# G1000_Buttons_Bottom.net
KiCad netlist of a schematic drawn in EasyEDA
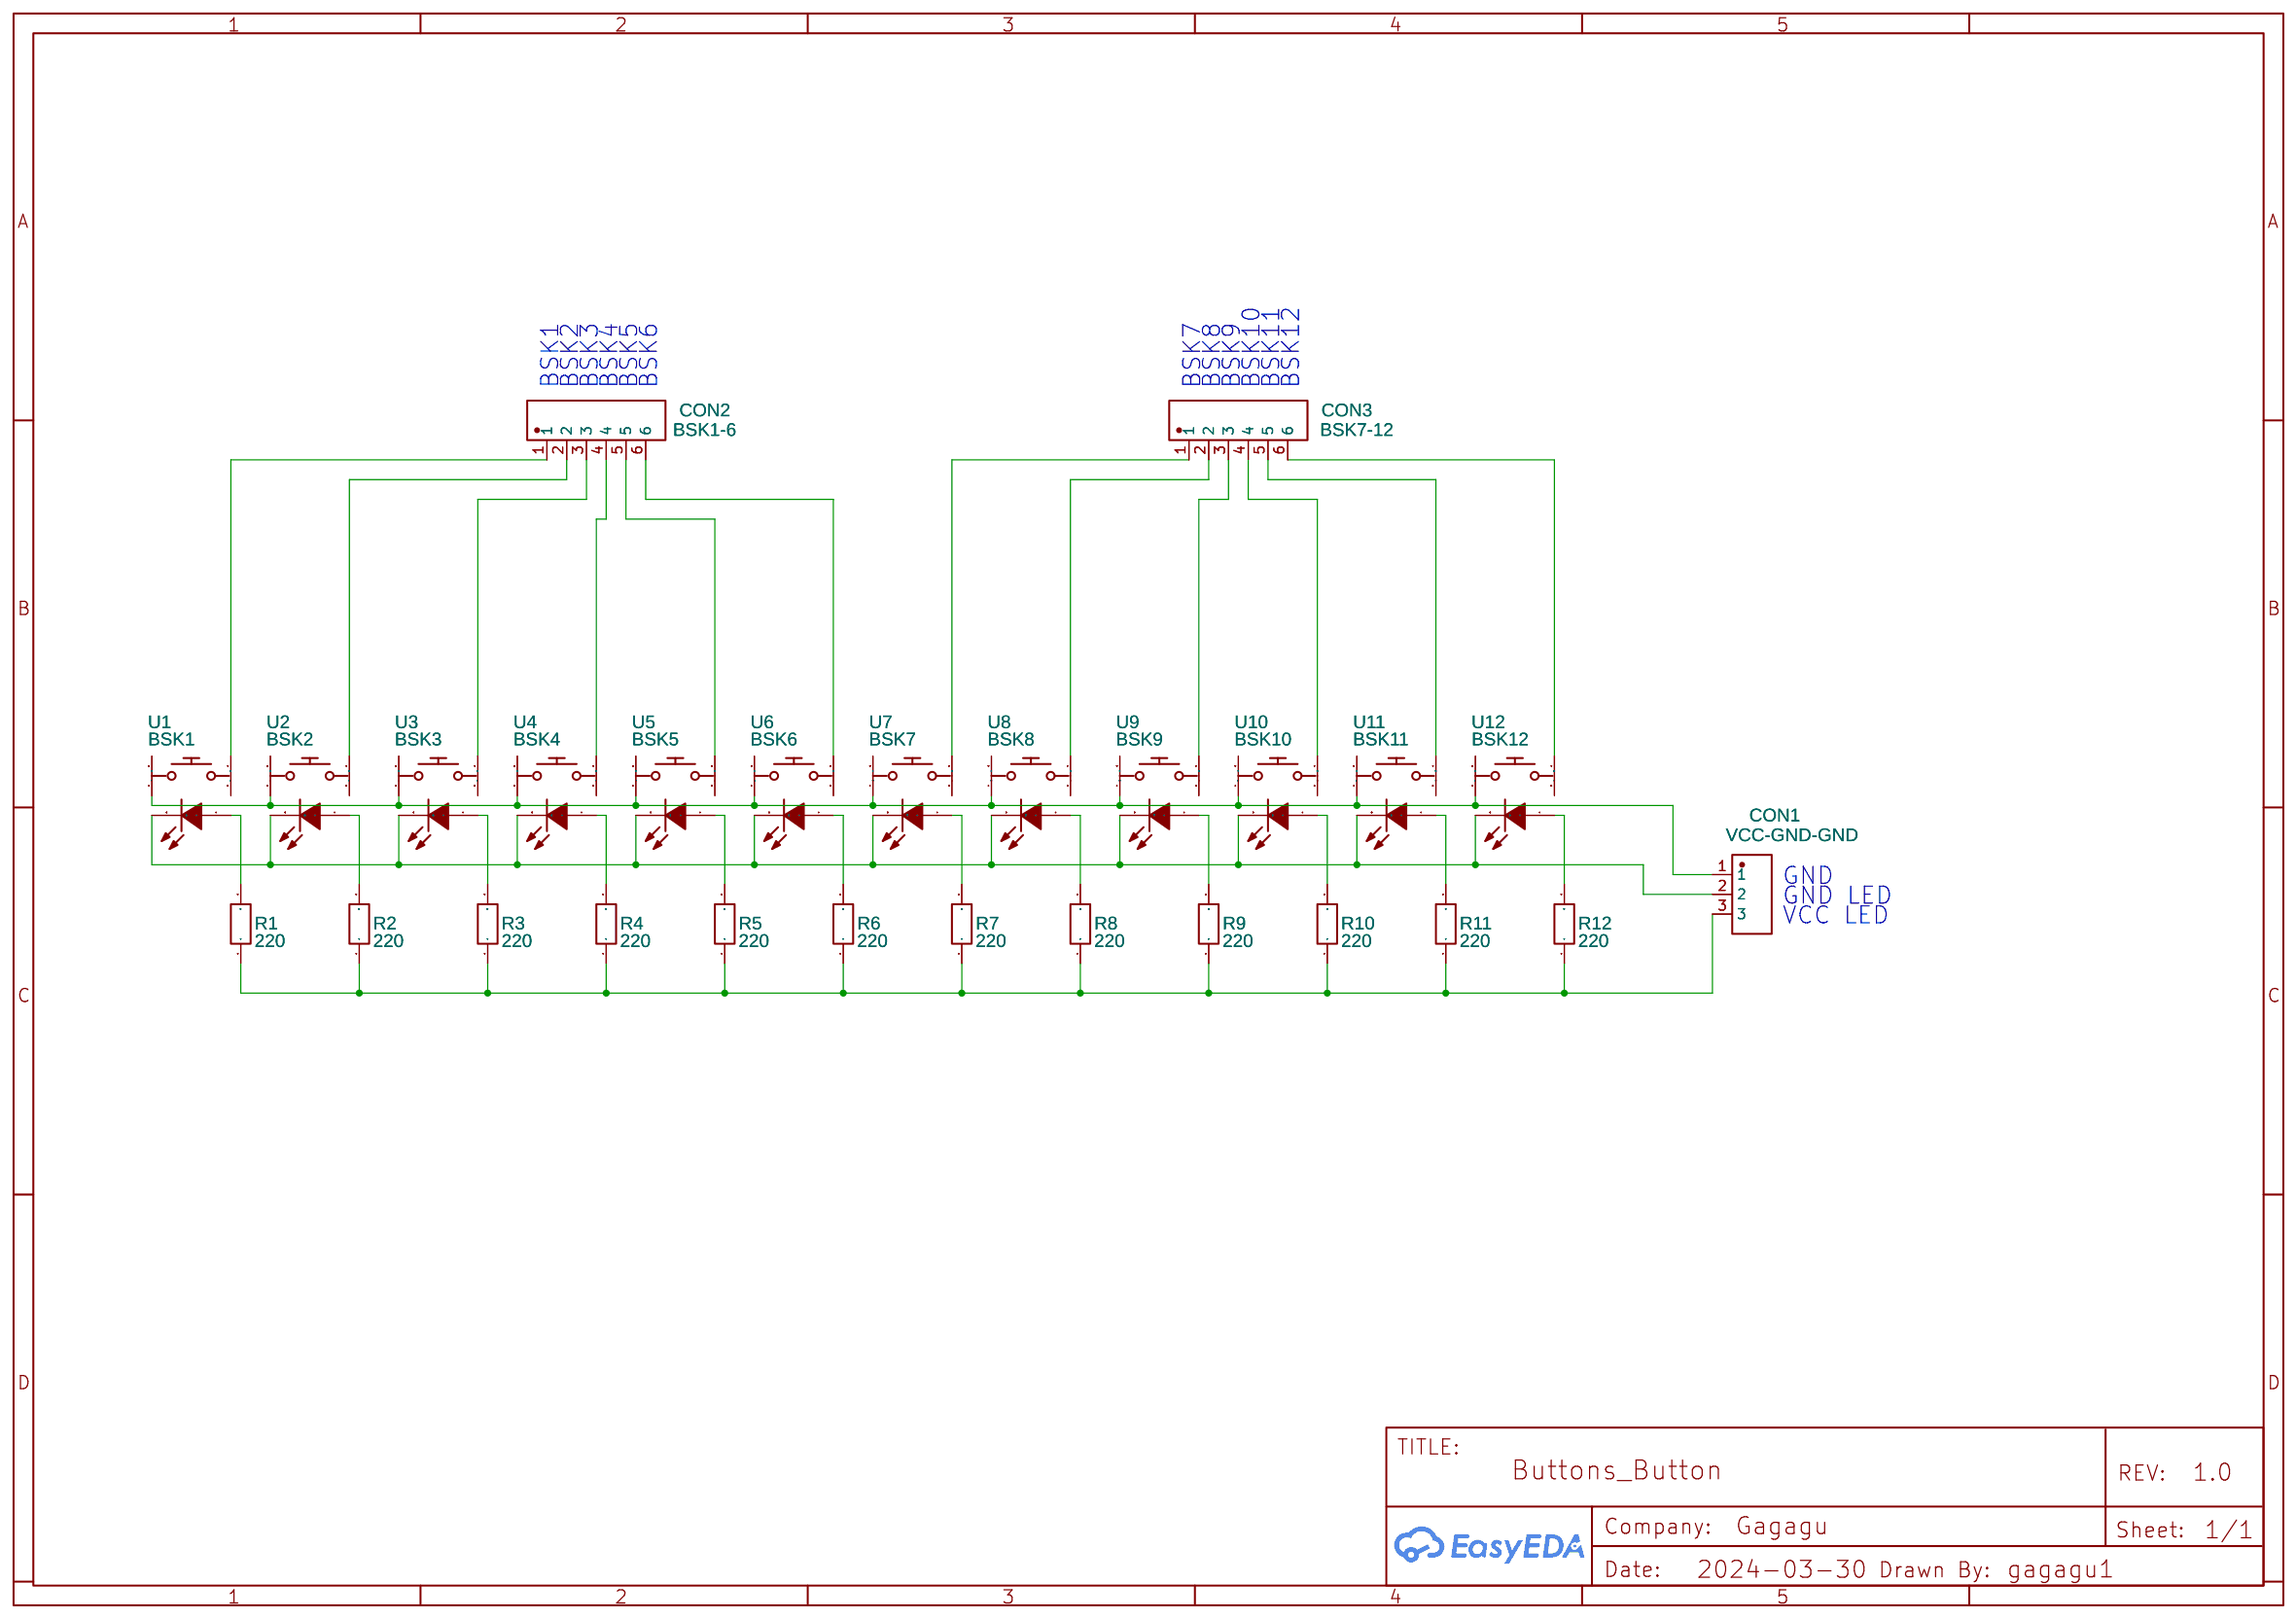
[diagram p0: schematic sheet]

(export (version "E")
  (design (tool "Eeschema 10.0.6"))
  (components
    (comp (ref "CON1")
      (value "VCC-GND-GND")
      (fields (field (name "Manufacturer Part") "HC-XH-3A-G") (field (name "Manufacturer") "HCTL(华灿天禄)"))
      (libsource (lib "") (part "HC-XH-3A-G"))
    )
    (comp (ref "CON2")
      (value "BSK1-6")
      (fields (field (name "Manufacturer Part") "XH-6A") (field (name "Manufacturer") "CAX"))
      (libsource (lib "") (part "ARUN-CONN-TH_XH-6A"))
    )
    (comp (ref "CON3")
      (value "BSK7-12")
      (fields (field (name "Manufacturer Part") "XH-6A") (field (name "Manufacturer") "CAX"))
      (libsource (lib "") (part "ARUN-CONN-TH_XH-6A"))
    )
    (comp (ref "R1") (value "220") (libsource (lib "") (part "R_AXIAL-0.4_EU")))
    (comp (ref "R2") (value "220") (libsource (lib "") (part "R_AXIAL-0.4_EU")))
    (comp (ref "R3") (value "220") (libsource (lib "") (part "R_AXIAL-0.4_EU")))
    (comp (ref "R4") (value "220") (libsource (lib "") (part "R_AXIAL-0.4_EU")))
    (comp (ref "R5") (value "220") (libsource (lib "") (part "R_AXIAL-0.4_EU")))
    (comp (ref "R6") (value "220") (libsource (lib "") (part "R_AXIAL-0.4_EU")))
    (comp (ref "R7") (value "220") (libsource (lib "") (part "R_AXIAL-0.4_EU")))
    (comp (ref "R8") (value "220") (libsource (lib "") (part "R_AXIAL-0.4_EU")))
    (comp (ref "R9") (value "220") (libsource (lib "") (part "R_AXIAL-0.4_EU")))
    (comp (ref "R10") (value "220") (libsource (lib "") (part "R_AXIAL-0.4_EU")))
    (comp (ref "R11") (value "220") (libsource (lib "") (part "R_AXIAL-0.4_EU")))
    (comp (ref "R12") (value "220") (libsource (lib "") (part "R_AXIAL-0.4_EU")))
    (comp (ref "U1") (value "BSK1") (libsource (lib "") (part "6X6_LED+PUSHBUTTON V2")))
    (comp (ref "U2") (value "BSK2") (libsource (lib "") (part "6X6_LED+PUSHBUTTON V2")))
    (comp (ref "U3") (value "BSK3") (libsource (lib "") (part "6X6_LED+PUSHBUTTON V2")))
    (comp (ref "U4") (value "BSK4") (libsource (lib "") (part "6X6_LED+PUSHBUTTON V2")))
    (comp (ref "U5") (value "BSK5") (libsource (lib "") (part "6X6_LED+PUSHBUTTON V2")))
    (comp (ref "U6") (value "BSK6") (libsource (lib "") (part "6X6_LED+PUSHBUTTON V2")))
    (comp (ref "U7") (value "BSK7") (libsource (lib "") (part "6X6_LED+PUSHBUTTON V2")))
    (comp (ref "U8") (value "BSK8") (libsource (lib "") (part "6X6_LED+PUSHBUTTON V2")))
    (comp (ref "U9") (value "BSK9") (libsource (lib "") (part "6X6_LED+PUSHBUTTON V2")))
    (comp (ref "U10") (value "BSK10") (libsource (lib "") (part "6X6_LED+PUSHBUTTON V2")))
    (comp (ref "U11") (value "BSK11") (libsource (lib "") (part "6X6_LED+PUSHBUTTON V2")))
    (comp (ref "U12") (value "BSK12") (libsource (lib "") (part "6X6_LED+PUSHBUTTON V2")))
  )
  (nets
    (net (code "1") (name "Net-(CON1-Pad1)") (class "Default")
      (node (ref "CON1") (pin "1") (pinfunction "1_1") (pintype "unspecified"))
      (node (ref "U1") (pin "4") (pinfunction "4_4") (pintype "unspecified"))
      (node (ref "U10") (pin "4") (pinfunction "4_4") (pintype "unspecified"))
      (node (ref "U11") (pin "4") (pinfunction "4_4") (pintype "unspecified"))
      (node (ref "U12") (pin "4") (pinfunction "4_4") (pintype "unspecified"))
      (node (ref "U2") (pin "4") (pinfunction "4_4") (pintype "unspecified"))
      (node (ref "U3") (pin "4") (pinfunction "4_4") (pintype "unspecified"))
      (node (ref "U4") (pin "4") (pinfunction "4_4") (pintype "unspecified"))
      (node (ref "U5") (pin "4") (pinfunction "4_4") (pintype "unspecified"))
      (node (ref "U6") (pin "4") (pinfunction "4_4") (pintype "unspecified"))
      (node (ref "U7") (pin "4") (pinfunction "4_4") (pintype "unspecified"))
      (node (ref "U8") (pin "4") (pinfunction "4_4") (pintype "unspecified"))
      (node (ref "U9") (pin "4") (pinfunction "4_4") (pintype "unspecified"))
    )
    (net (code "2") (name "Net-(CON1-Pad2)") (class "Default")
      (node (ref "CON1") (pin "2") (pinfunction "2_2") (pintype "unspecified"))
      (node (ref "U1") (pin "C") (pinfunction "C_C") (pintype "unspecified"))
      (node (ref "U10") (pin "C") (pinfunction "C_C") (pintype "unspecified"))
      (node (ref "U11") (pin "C") (pinfunction "C_C") (pintype "unspecified"))
      (node (ref "U12") (pin "C") (pinfunction "C_C") (pintype "unspecified"))
      (node (ref "U2") (pin "C") (pinfunction "C_C") (pintype "unspecified"))
      (node (ref "U3") (pin "C") (pinfunction "C_C") (pintype "unspecified"))
      (node (ref "U4") (pin "C") (pinfunction "C_C") (pintype "unspecified"))
      (node (ref "U5") (pin "C") (pinfunction "C_C") (pintype "unspecified"))
      (node (ref "U6") (pin "C") (pinfunction "C_C") (pintype "unspecified"))
      (node (ref "U7") (pin "C") (pinfunction "C_C") (pintype "unspecified"))
      (node (ref "U8") (pin "C") (pinfunction "C_C") (pintype "unspecified"))
      (node (ref "U9") (pin "C") (pinfunction "C_C") (pintype "unspecified"))
    )
    (net (code "3") (name "Net-(CON1-Pad3)") (class "Default")
      (node (ref "CON1") (pin "3") (pinfunction "3_3") (pintype "unspecified"))
      (node (ref "R1") (pin "1") (pinfunction "1_1") (pintype "unspecified"))
      (node (ref "R10") (pin "1") (pinfunction "1_1") (pintype "unspecified"))
      (node (ref "R11") (pin "1") (pinfunction "1_1") (pintype "unspecified"))
      (node (ref "R12") (pin "1") (pinfunction "1_1") (pintype "unspecified"))
      (node (ref "R2") (pin "1") (pinfunction "1_1") (pintype "unspecified"))
      (node (ref "R3") (pin "1") (pinfunction "1_1") (pintype "unspecified"))
      (node (ref "R4") (pin "1") (pinfunction "1_1") (pintype "unspecified"))
      (node (ref "R5") (pin "1") (pinfunction "1_1") (pintype "unspecified"))
      (node (ref "R6") (pin "1") (pinfunction "1_1") (pintype "unspecified"))
      (node (ref "R7") (pin "1") (pinfunction "1_1") (pintype "unspecified"))
      (node (ref "R8") (pin "1") (pinfunction "1_1") (pintype "unspecified"))
      (node (ref "R9") (pin "1") (pinfunction "1_1") (pintype "unspecified"))
    )
    (net (code "4") (name "Net-(CON2-Pad1)") (class "Default")
      (node (ref "CON2") (pin "1") (pinfunction "1_1") (pintype "unspecified"))
      (node (ref "U1") (pin "1") (pinfunction "1_1") (pintype "unspecified"))
    )
    (net (code "5") (name "Net-(CON2-Pad2)") (class "Default")
      (node (ref "CON2") (pin "2") (pinfunction "2_2") (pintype "unspecified"))
      (node (ref "U2") (pin "1") (pinfunction "1_1") (pintype "unspecified"))
    )
    (net (code "6") (name "Net-(CON2-Pad3)") (class "Default")
      (node (ref "CON2") (pin "3") (pinfunction "3_3") (pintype "unspecified"))
      (node (ref "U3") (pin "1") (pinfunction "1_1") (pintype "unspecified"))
    )
    (net (code "7") (name "Net-(CON2-Pad4)") (class "Default")
      (node (ref "CON2") (pin "4") (pinfunction "4_4") (pintype "unspecified"))
      (node (ref "U4") (pin "1") (pinfunction "1_1") (pintype "unspecified"))
    )
    (net (code "8") (name "Net-(CON2-Pad5)") (class "Default")
      (node (ref "CON2") (pin "5") (pinfunction "5_5") (pintype "unspecified"))
      (node (ref "U5") (pin "1") (pinfunction "1_1") (pintype "unspecified"))
    )
    (net (code "9") (name "Net-(CON2-Pad6)") (class "Default")
      (node (ref "CON2") (pin "6") (pinfunction "6_6") (pintype "unspecified"))
      (node (ref "U6") (pin "1") (pinfunction "1_1") (pintype "unspecified"))
    )
    (net (code "10") (name "Net-(CON3-Pad1)") (class "Default")
      (node (ref "CON3") (pin "1") (pinfunction "1_1") (pintype "unspecified"))
      (node (ref "U7") (pin "1") (pinfunction "1_1") (pintype "unspecified"))
    )
    (net (code "11") (name "Net-(CON3-Pad2)") (class "Default")
      (node (ref "CON3") (pin "2") (pinfunction "2_2") (pintype "unspecified"))
      (node (ref "U8") (pin "1") (pinfunction "1_1") (pintype "unspecified"))
    )
    (net (code "12") (name "Net-(CON3-Pad3)") (class "Default")
      (node (ref "CON3") (pin "3") (pinfunction "3_3") (pintype "unspecified"))
      (node (ref "U9") (pin "1") (pinfunction "1_1") (pintype "unspecified"))
    )
    (net (code "13") (name "Net-(CON3-Pad4)") (class "Default")
      (node (ref "CON3") (pin "4") (pinfunction "4_4") (pintype "unspecified"))
      (node (ref "U10") (pin "1") (pinfunction "1_1") (pintype "unspecified"))
    )
    (net (code "14") (name "Net-(CON3-Pad5)") (class "Default")
      (node (ref "CON3") (pin "5") (pinfunction "5_5") (pintype "unspecified"))
      (node (ref "U11") (pin "1") (pinfunction "1_1") (pintype "unspecified"))
    )
    (net (code "15") (name "Net-(CON3-Pad6)") (class "Default")
      (node (ref "CON3") (pin "6") (pinfunction "6_6") (pintype "unspecified"))
      (node (ref "U12") (pin "1") (pinfunction "1_1") (pintype "unspecified"))
    )
    (net (code "16") (name "Net-(R1-Pad2)") (class "Default")
      (node (ref "R1") (pin "2") (pinfunction "2_2") (pintype "unspecified"))
      (node (ref "U1") (pin "A") (pinfunction "A_A") (pintype "unspecified"))
    )
    (net (code "17") (name "Net-(R2-Pad2)") (class "Default")
      (node (ref "R2") (pin "2") (pinfunction "2_2") (pintype "unspecified"))
      (node (ref "U2") (pin "A") (pinfunction "A_A") (pintype "unspecified"))
    )
    (net (code "18") (name "Net-(R3-Pad2)") (class "Default")
      (node (ref "R3") (pin "2") (pinfunction "2_2") (pintype "unspecified"))
      (node (ref "U3") (pin "A") (pinfunction "A_A") (pintype "unspecified"))
    )
    (net (code "19") (name "Net-(R4-Pad2)") (class "Default")
      (node (ref "R4") (pin "2") (pinfunction "2_2") (pintype "unspecified"))
      (node (ref "U4") (pin "A") (pinfunction "A_A") (pintype "unspecified"))
    )
    (net (code "20") (name "Net-(R5-Pad2)") (class "Default")
      (node (ref "R5") (pin "2") (pinfunction "2_2") (pintype "unspecified"))
      (node (ref "U5") (pin "A") (pinfunction "A_A") (pintype "unspecified"))
    )
    (net (code "21") (name "Net-(R6-Pad2)") (class "Default")
      (node (ref "R6") (pin "2") (pinfunction "2_2") (pintype "unspecified"))
      (node (ref "U6") (pin "A") (pinfunction "A_A") (pintype "unspecified"))
    )
    (net (code "22") (name "Net-(R7-Pad2)") (class "Default")
      (node (ref "R7") (pin "2") (pinfunction "2_2") (pintype "unspecified"))
      (node (ref "U7") (pin "A") (pinfunction "A_A") (pintype "unspecified"))
    )
    (net (code "23") (name "Net-(R8-Pad2)") (class "Default")
      (node (ref "R8") (pin "2") (pinfunction "2_2") (pintype "unspecified"))
      (node (ref "U8") (pin "A") (pinfunction "A_A") (pintype "unspecified"))
    )
    (net (code "24") (name "Net-(R9-Pad2)") (class "Default")
      (node (ref "R9") (pin "2") (pinfunction "2_2") (pintype "unspecified"))
      (node (ref "U9") (pin "A") (pinfunction "A_A") (pintype "unspecified"))
    )
    (net (code "25") (name "Net-(R10-Pad2)") (class "Default")
      (node (ref "R10") (pin "2") (pinfunction "2_2") (pintype "unspecified"))
      (node (ref "U10") (pin "A") (pinfunction "A_A") (pintype "unspecified"))
    )
    (net (code "26") (name "Net-(R11-Pad2)") (class "Default")
      (node (ref "R11") (pin "2") (pinfunction "2_2") (pintype "unspecified"))
      (node (ref "U11") (pin "A") (pinfunction "A_A") (pintype "unspecified"))
    )
    (net (code "27") (name "Net-(R12-Pad2)") (class "Default")
      (node (ref "R12") (pin "2") (pinfunction "2_2") (pintype "unspecified"))
      (node (ref "U12") (pin "A") (pinfunction "A_A") (pintype "unspecified"))
    )
    (net (code "28") (name "unconnected-(U1-Pad2)") (class "Default")
      (node (ref "U1") (pin "2") (pinfunction "2_2") (pintype "unspecified"))
    )
    (net (code "29") (name "unconnected-(U1-Pad3)") (class "Default")
      (node (ref "U1") (pin "3") (pinfunction "3_3") (pintype "unspecified"))
    )
    (net (code "30") (name "unconnected-(U2-Pad2)") (class "Default")
      (node (ref "U2") (pin "2") (pinfunction "2_2") (pintype "unspecified"))
    )
    (net (code "31") (name "unconnected-(U2-Pad3)") (class "Default")
      (node (ref "U2") (pin "3") (pinfunction "3_3") (pintype "unspecified"))
    )
    (net (code "32") (name "unconnected-(U3-Pad2)") (class "Default")
      (node (ref "U3") (pin "2") (pinfunction "2_2") (pintype "unspecified"))
    )
    (net (code "33") (name "unconnected-(U3-Pad3)") (class "Default")
      (node (ref "U3") (pin "3") (pinfunction "3_3") (pintype "unspecified"))
    )
    (net (code "34") (name "unconnected-(U4-Pad2)") (class "Default")
      (node (ref "U4") (pin "2") (pinfunction "2_2") (pintype "unspecified"))
    )
    (net (code "35") (name "unconnected-(U4-Pad3)") (class "Default")
      (node (ref "U4") (pin "3") (pinfunction "3_3") (pintype "unspecified"))
    )
    (net (code "36") (name "unconnected-(U5-Pad2)") (class "Default")
      (node (ref "U5") (pin "2") (pinfunction "2_2") (pintype "unspecified"))
    )
    (net (code "37") (name "unconnected-(U5-Pad3)") (class "Default")
      (node (ref "U5") (pin "3") (pinfunction "3_3") (pintype "unspecified"))
    )
    (net (code "38") (name "unconnected-(U6-Pad2)") (class "Default")
      (node (ref "U6") (pin "2") (pinfunction "2_2") (pintype "unspecified"))
    )
    (net (code "39") (name "unconnected-(U6-Pad3)") (class "Default")
      (node (ref "U6") (pin "3") (pinfunction "3_3") (pintype "unspecified"))
    )
    (net (code "40") (name "unconnected-(U7-Pad2)") (class "Default")
      (node (ref "U7") (pin "2") (pinfunction "2_2") (pintype "unspecified"))
    )
    (net (code "41") (name "unconnected-(U7-Pad3)") (class "Default")
      (node (ref "U7") (pin "3") (pinfunction "3_3") (pintype "unspecified"))
    )
    (net (code "42") (name "unconnected-(U8-Pad2)") (class "Default")
      (node (ref "U8") (pin "2") (pinfunction "2_2") (pintype "unspecified"))
    )
    (net (code "43") (name "unconnected-(U8-Pad3)") (class "Default")
      (node (ref "U8") (pin "3") (pinfunction "3_3") (pintype "unspecified"))
    )
    (net (code "44") (name "unconnected-(U9-Pad2)") (class "Default")
      (node (ref "U9") (pin "2") (pinfunction "2_2") (pintype "unspecified"))
    )
    (net (code "45") (name "unconnected-(U9-Pad3)") (class "Default")
      (node (ref "U9") (pin "3") (pinfunction "3_3") (pintype "unspecified"))
    )
    (net (code "46") (name "unconnected-(U10-Pad2)") (class "Default")
      (node (ref "U10") (pin "2") (pinfunction "2_2") (pintype "unspecified"))
    )
    (net (code "47") (name "unconnected-(U10-Pad3)") (class "Default")
      (node (ref "U10") (pin "3") (pinfunction "3_3") (pintype "unspecified"))
    )
    (net (code "48") (name "unconnected-(U11-Pad2)") (class "Default")
      (node (ref "U11") (pin "2") (pinfunction "2_2") (pintype "unspecified"))
    )
    (net (code "49") (name "unconnected-(U11-Pad3)") (class "Default")
      (node (ref "U11") (pin "3") (pinfunction "3_3") (pintype "unspecified"))
    )
    (net (code "50") (name "unconnected-(U12-Pad2)") (class "Default")
      (node (ref "U12") (pin "2") (pinfunction "2_2") (pintype "unspecified"))
    )
    (net (code "51") (name "unconnected-(U12-Pad3)") (class "Default")
      (node (ref "U12") (pin "3") (pinfunction "3_3") (pintype "unspecified"))
    )
  )
)
